# Pressure_Sensor.net
KiCad netlist of a schematic drawn in EAGLE
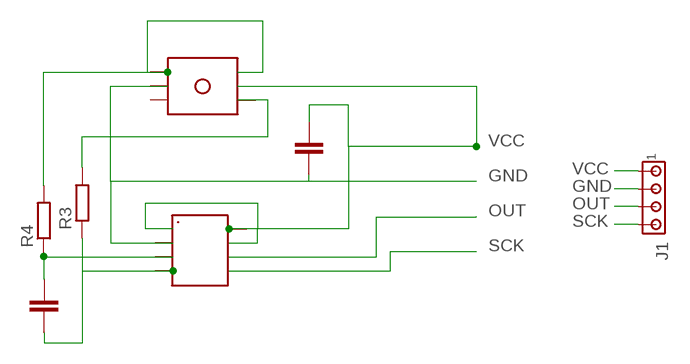
[diagram p0: schematic, sheet 1]

(export (version "E")
  (design (tool "Eeschema 10.0.6"))
  (components
    (comp (ref "C1")
      (value "100n")
      (footprint "eagle-import:C0805")
      (libsource (lib "eagle-import") (part "C-EUC0805"))
    )
    (comp (ref "C2")
      (value "100n")
      (footprint "eagle-import:C0805")
      (libsource (lib "eagle-import") (part "C-EUC0805"))
    )
    (comp (ref "J1")
      (value "MTA04-100")
      (footprint "eagle-import:10X04MTA")
      (libsource (lib "eagle-import") (part "MTA04-100"))
    )
    (comp (ref "R3")
      (value "R-EU_R0805")
      (footprint "eagle-import:R0805")
      (libsource (lib "eagle-import") (part "R-EU_R0805"))
    )
    (comp (ref "R4")
      (value "R-EU_R0805")
      (footprint "eagle-import:R0805")
      (libsource (lib "eagle-import") (part "R-EU_R0805"))
    )
    (comp (ref "U$1")
      (value "HX710B")
      (footprint "eagle-import:HX710B")
      (libsource (lib "eagle-import") (part "HX710B"))
    )
    (comp (ref "U$2")
      (value "PRESSURE")
      (footprint "eagle-import:PRESSURE")
      (libsource (lib "eagle-import") (part "PRESSURE"))
    )
  )
  (nets
    (net (code "1") (name "/GND") (class "Default")
      (node (ref "C1") (pin "2") (pinfunction "2_2") (pintype "passive"))
      (node (ref "J1") (pin "2") (pinfunction "2_2") (pintype "passive"))
      (node (ref "U$1") (pin "AGND") (pinfunction "AGND_AGND") (pintype "bidirectional"))
      (node (ref "U$2") (pin "2") (pinfunction "2_2") (pintype "bidirectional"))
    )
    (net (code "2") (name "/OUT") (class "Default")
      (node (ref "J1") (pin "3") (pinfunction "3_3") (pintype "passive"))
      (node (ref "U$1") (pin "DOUT") (pinfunction "DOUT_DOUT") (pintype "bidirectional"))
    )
    (net (code "3") (name "/SCK") (class "Default")
      (node (ref "J1") (pin "4") (pinfunction "4_4") (pintype "passive"))
      (node (ref "U$1") (pin "SCK") (pinfunction "SCK_SCK") (pintype "bidirectional"))
    )
    (net (code "4") (name "/VCC") (class "Default")
      (node (ref "C1") (pin "1") (pinfunction "1_1") (pintype "passive"))
      (node (ref "J1") (pin "1") (pinfunction "1_1") (pintype "passive"))
      (node (ref "U$1") (pin "AVDD") (pinfunction "AVDD_AVDD") (pintype "bidirectional"))
      (node (ref "U$1") (pin "DVDD") (pinfunction "DVDD_DVDD") (pintype "bidirectional"))
      (node (ref "U$1") (pin "VREF") (pinfunction "VREF_VREF") (pintype "bidirectional"))
      (node (ref "U$2") (pin "5") (pinfunction "5_5") (pintype "bidirectional"))
    )
    (net (code "5") (name "Net-(C2-Pad1)") (class "Default")
      (node (ref "C2") (pin "1") (pinfunction "1_1") (pintype "passive"))
      (node (ref "R3") (pin "1") (pinfunction "1_1") (pintype "passive"))
      (node (ref "U$1") (pin "INP") (pinfunction "INP_INP") (pintype "bidirectional"))
    )
    (net (code "6") (name "Net-(C2-Pad2)") (class "Default")
      (node (ref "C2") (pin "2") (pinfunction "2_2") (pintype "passive"))
      (node (ref "R4") (pin "1") (pinfunction "1_1") (pintype "passive"))
      (node (ref "U$1") (pin "INN") (pinfunction "INN_INN") (pintype "bidirectional"))
    )
    (net (code "7") (name "Net-(R3-Pad2)") (class "Default")
      (node (ref "R3") (pin "2") (pinfunction "2_2") (pintype "passive"))
      (node (ref "U$2") (pin "4") (pinfunction "4_4") (pintype "bidirectional"))
    )
    (net (code "8") (name "Net-(R4-Pad2)") (class "Default")
      (node (ref "R4") (pin "2") (pinfunction "2_2") (pintype "passive"))
      (node (ref "U$2") (pin "1") (pinfunction "1_1") (pintype "bidirectional"))
      (node (ref "U$2") (pin "6") (pinfunction "6_6") (pintype "bidirectional"))
    )
    (net (code "9") (name "unconnected-(U$2-Pad3)") (class "Default")
      (node (ref "U$2") (pin "3") (pinfunction "3_3") (pintype "bidirectional"))
    )
  )
)
